# PSPS_AVNC_SRD_power-2020-09-19.net
KiCad netlist of a schematic drawn in EAGLE
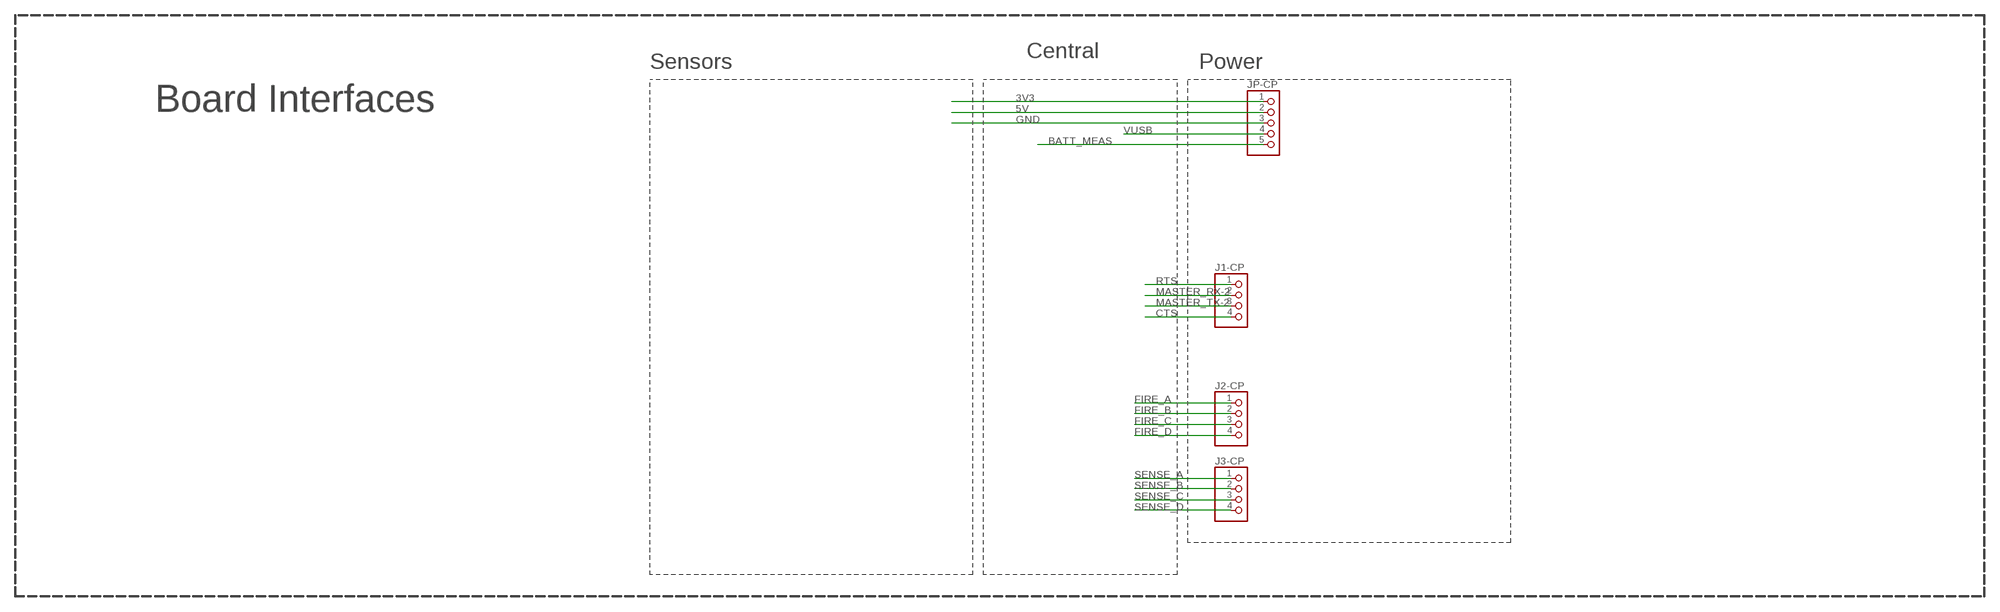
[diagram p0: schematic, sheet 1, part 1 of 3]
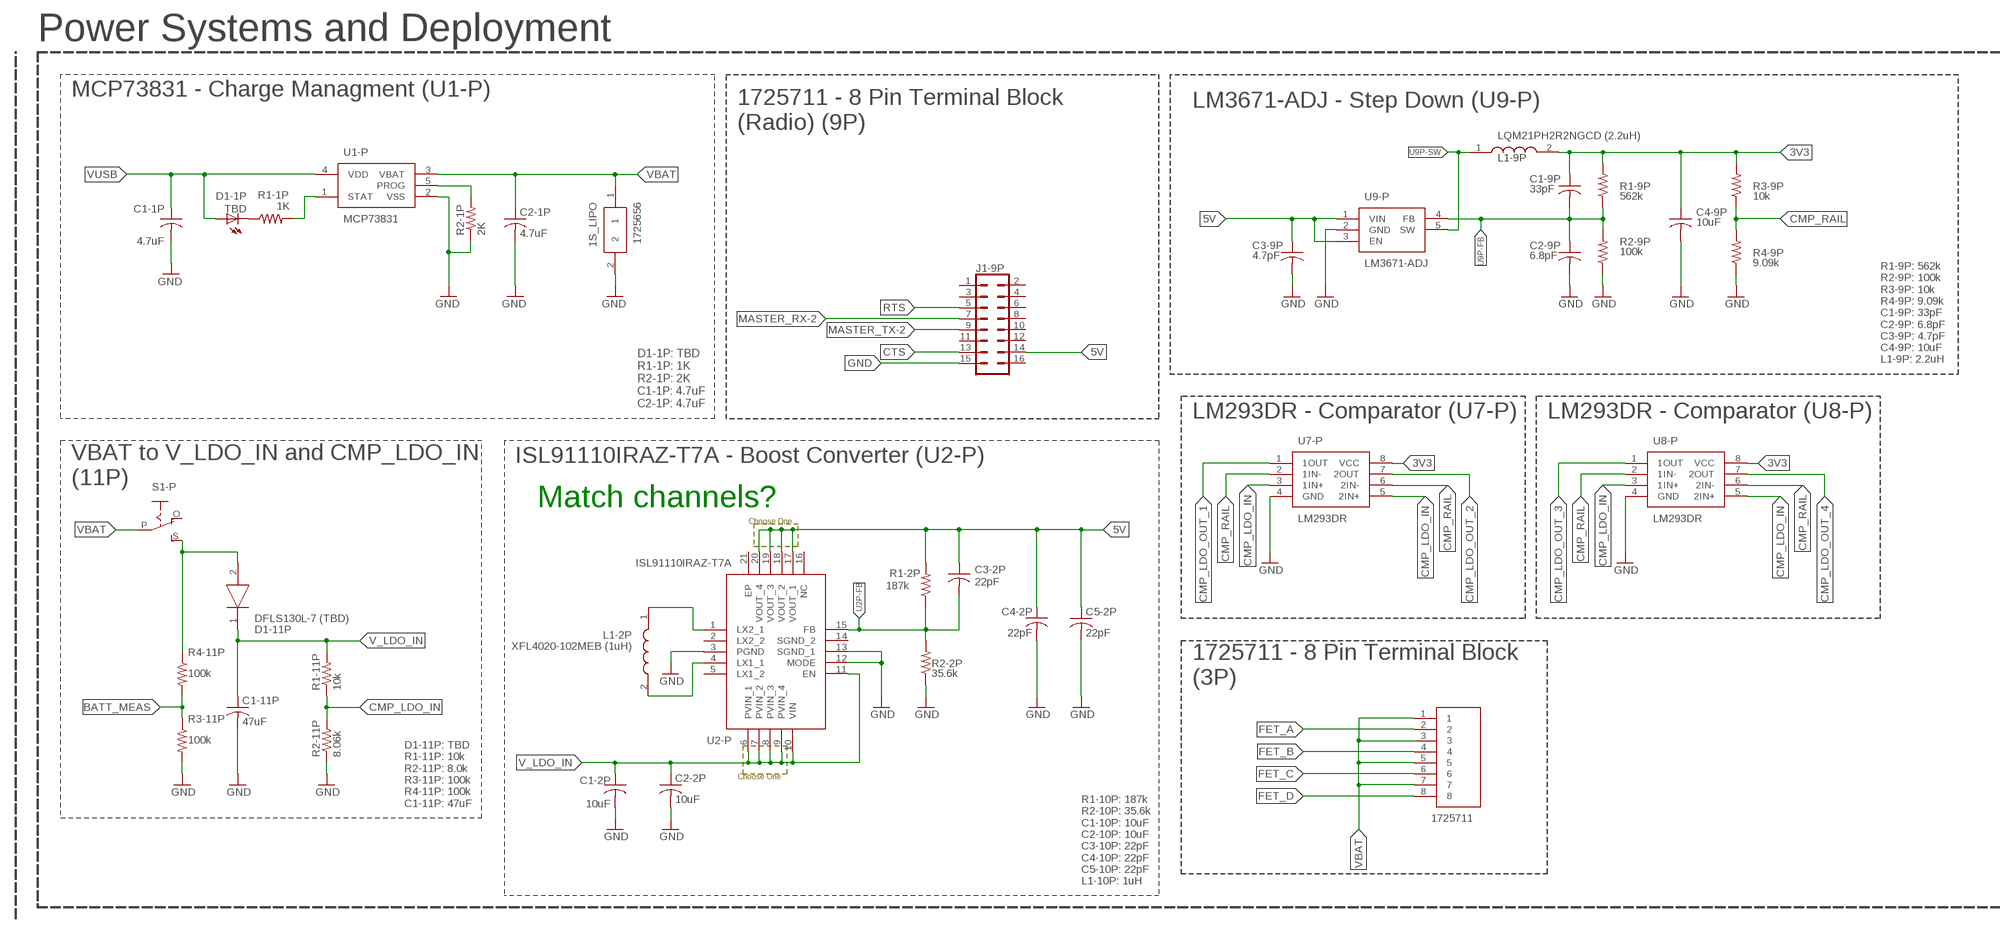
[diagram p1: schematic, sheet 1, part 2 of 3]
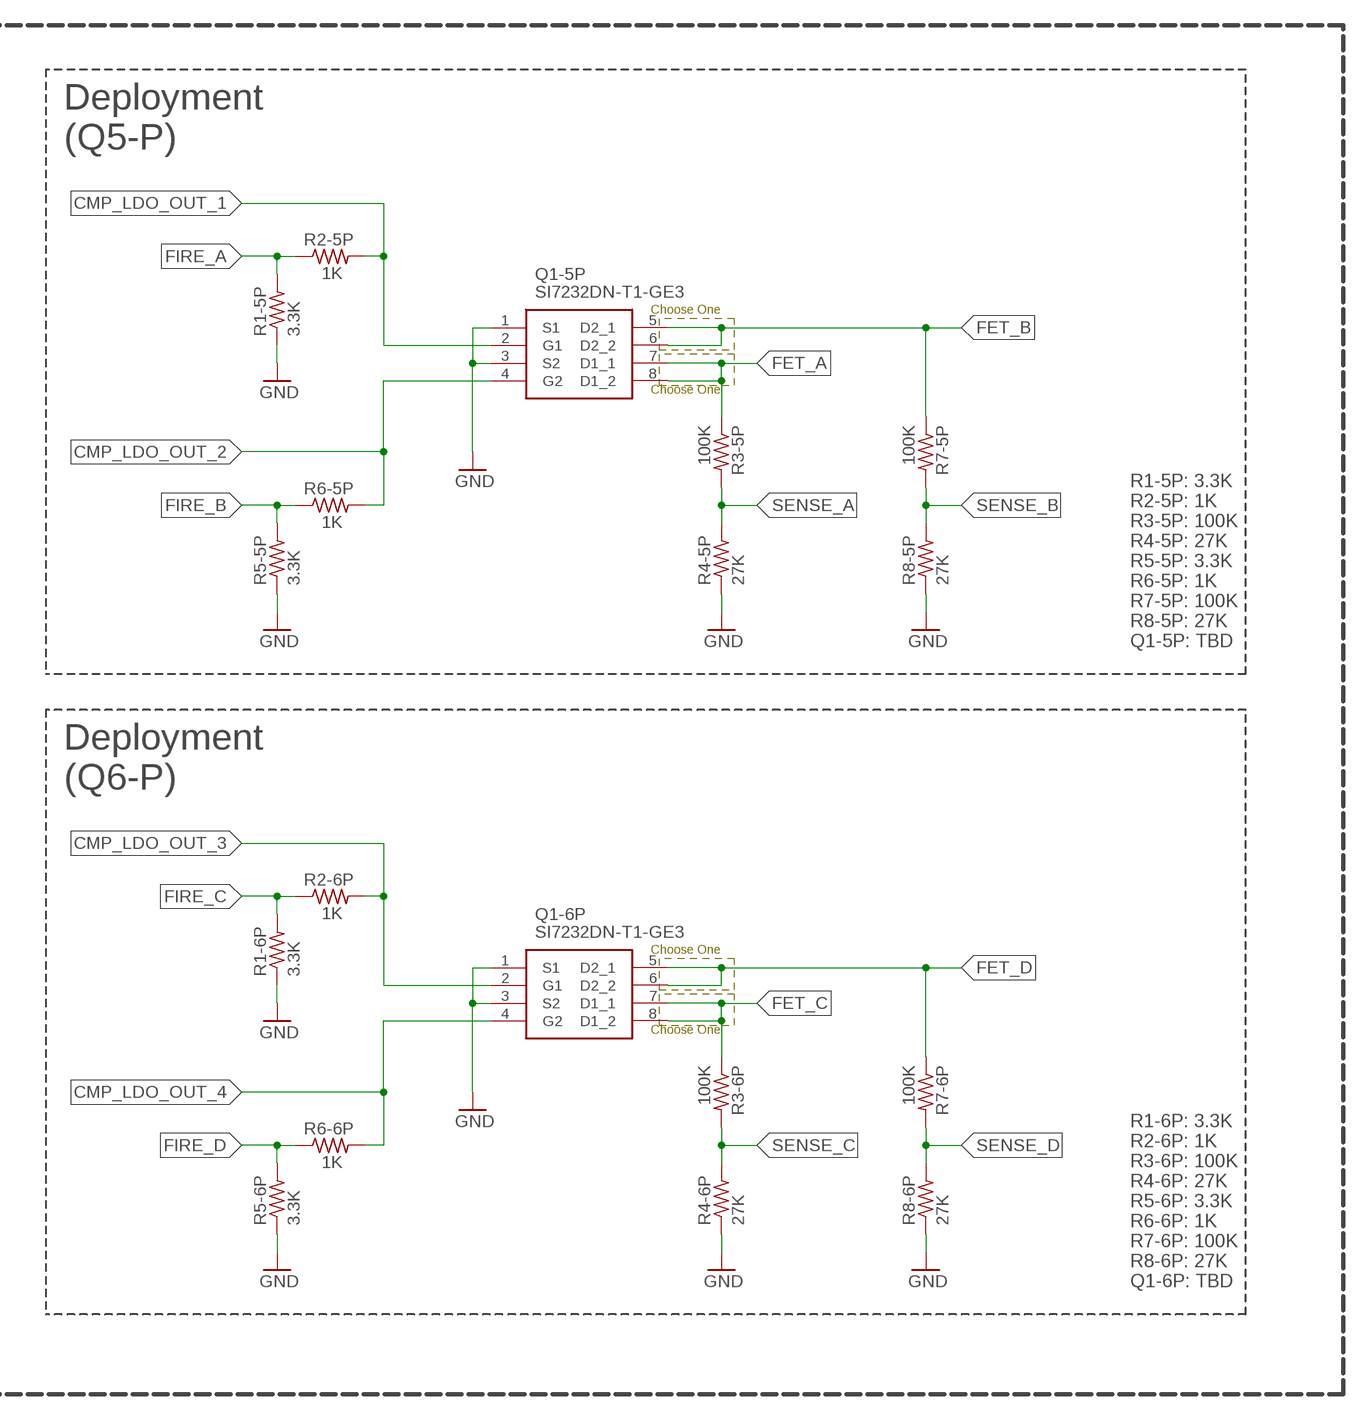
[diagram p2: schematic, sheet 1, part 3 of 3]

(export (version "E")
  (design (tool "Eeschema 10.0.6"))
  (components
    (comp (ref "1S_LIPO")
      (value "1725656")
      (footprint "eagle-import:1725656")
      (fields (field (name "MOUSER_PART_NUMBER") "651-1725656"))
      (libsource (lib "eagle-import") (part "1725656"))
    )
    (comp (ref "C1-1P")
      (value "4.7uF")
      (footprint "eagle-import:C0805")
      (libsource (lib "eagle-import") (part "resistor_348_C-USC0805"))
    )
    (comp (ref "C1-2P")
      (value "10uF")
      (footprint "eagle-import:C0805")
      (libsource (lib "eagle-import") (part "resistor_348_C-USC0805"))
    )
    (comp (ref "C1-9P")
      (value "33pF")
      (footprint "eagle-import:C0805")
      (libsource (lib "eagle-import") (part "resistor_348_C-USC0805"))
    )
    (comp (ref "C1-11P")
      (value "47uF")
      (footprint "eagle-import:C0805")
      (libsource (lib "eagle-import") (part "resistor_348_C-USC0805"))
    )
    (comp (ref "C2-1P")
      (value "4.7uF")
      (footprint "eagle-import:C0805")
      (libsource (lib "eagle-import") (part "resistor_348_C-USC0805"))
    )
    (comp (ref "C2-2P")
      (value "10uF")
      (footprint "eagle-import:C0805")
      (libsource (lib "eagle-import") (part "C-USC0805"))
    )
    (comp (ref "C2-9P")
      (value "6.8pF")
      (footprint "eagle-import:C0805")
      (libsource (lib "eagle-import") (part "resistor_348_C-USC0805"))
    )
    (comp (ref "C3-2P")
      (value "22pF")
      (footprint "eagle-import:C0805")
      (libsource (lib "eagle-import") (part "resistor_348_C-USC0805"))
    )
    (comp (ref "C3-9P")
      (value "4.7pF")
      (footprint "eagle-import:C0805")
      (libsource (lib "eagle-import") (part "resistor_348_C-USC0805"))
    )
    (comp (ref "C4-2P")
      (value "22pF")
      (footprint "eagle-import:C0805")
      (fields (field (name "SPICEPREFIX") "C"))
      (libsource (lib "eagle-import") (part "resistor_348_C-USC0805"))
    )
    (comp (ref "C4-9P")
      (value "10uF")
      (footprint "eagle-import:C0805")
      (libsource (lib "eagle-import") (part "resistor_348_C-USC0805"))
    )
    (comp (ref "C5-2P")
      (value "22pF")
      (footprint "eagle-import:C0805")
      (libsource (lib "eagle-import") (part "C-USC0805"))
    )
    (comp (ref "D1-1P")
      (value "TBD")
      (footprint "eagle-import:CHIPLED_0805")
      (libsource (lib "eagle-import") (part "LEDCHIPLED_0805"))
    )
    (comp (ref "D1-11P")
      (value "DFLS130L-7 (TBD)")
      (footprint "eagle-import:POWERDI_123")
      (fields
        (field (name "MANUFACTURER_PART_NUMBER") "DFLS130L-7")
        (field (name "MOUSER_PART_NUMBER") "621-DFLS130L")
      )
      (libsource (lib "eagle-import") (part "DFLS130L-7"))
    )
    (comp (ref "J1-9P")
      (value "CONN_08X2")
      (footprint "eagle-import:2X8")
      (libsource (lib "eagle-import") (part "CONN_08X2"))
    )
    (comp (ref "J1-CP")
      (value "PINHD-1X4")
      (footprint "eagle-import:1X04")
      (libsource (lib "eagle-import") (part "PINHD-1X4"))
    )
    (comp (ref "J2-CP")
      (value "PINHD-1X4")
      (footprint "eagle-import:1X04")
      (libsource (lib "eagle-import") (part "PINHD-1X4"))
    )
    (comp (ref "J2-P")
      (value "1725711")
      (footprint "eagle-import:1725711")
      (fields (field (name "MOUSER_PART_NUMBER") "651-1725711"))
      (libsource (lib "eagle-import") (part "1725711"))
    )
    (comp (ref "J3-CP")
      (value "PINHD-1X4")
      (footprint "eagle-import:1X04")
      (libsource (lib "eagle-import") (part "PINHD-1X4"))
    )
    (comp (ref "JP-CP")
      (value "PINHD-1X5")
      (footprint "eagle-import:1X05")
      (libsource (lib "eagle-import") (part "PINHD-1X5"))
    )
    (comp (ref "L1-2P")
      (value "XFL4020-102MEB (1uH)")
      (footprint "eagle-import:XFL4020")
      (fields
        (field (name "MANUFACTURER_PART_NUMBER") "XFL4020-102MEB")
        (field (name "MOUSER_PART_NUMBER") "994-XFL4020-102MEB")
      )
      (libsource (lib "eagle-import") (part "XFL4020-102MEB"))
    )
    (comp (ref "L1-9P")
      (value "LQM21PH2R2NGCD (2.2uH)")
      (footprint "eagle-import:INDC2012X100N")
      (fields
        (field (name "MANUFACTURER_PART_NUMBER") "LQM21PH2R2NGCD")
        (field (name "MOUSER_PART_NUMBER") "81-LQM21PH2R2NGCD")
      )
      (libsource (lib "eagle-import") (part "LQM21PH2R2NGCD"))
    )
    (comp (ref "Q1-5P")
      (value "SI7232DN-T1-GE3")
      (footprint "eagle-import:POWERPAK-1212-8")
      (fields (field (name "MOUSER_PART_NUMBER") "781-SI7232DN-GE3"))
      (libsource (lib "eagle-import") (part "SI7232DN-T1-GE3"))
    )
    (comp (ref "Q1-6P")
      (value "SI7232DN-T1-GE3")
      (footprint "eagle-import:POWERPAK-1212-8")
      (fields (field (name "MOUSER_PART_NUMBER") "781-SI7232DN-GE3"))
      (libsource (lib "eagle-import") (part "SI7232DN-T1-GE3"))
    )
    (comp (ref "R1-1P")
      (value "1K")
      (footprint "eagle-import:R0805")
      (libsource (lib "eagle-import") (part "resistor_348_R-US_R0805"))
    )
    (comp (ref "R1-2P")
      (value "187k")
      (footprint "eagle-import:R0805")
      (libsource (lib "eagle-import") (part "resistor_348_R-US_R0805"))
    )
    (comp (ref "R1-5P")
      (value "3.3K")
      (footprint "eagle-import:M0805")
      (libsource (lib "eagle-import") (part "rcl_334_R-US_M0805"))
    )
    (comp (ref "R1-6P")
      (value "3.3K")
      (footprint "eagle-import:M0805")
      (libsource (lib "eagle-import") (part "rcl_334_R-US_M0805"))
    )
    (comp (ref "R1-9P")
      (value "562k")
      (footprint "eagle-import:R0805")
      (libsource (lib "eagle-import") (part "resistor_348_R-US_R0805"))
    )
    (comp (ref "R1-11P")
      (value "10k")
      (footprint "eagle-import:R0805")
      (libsource (lib "eagle-import") (part "resistor_348_R-US_R0805"))
    )
    (comp (ref "R2-1P")
      (value "2K")
      (footprint "eagle-import:R0805")
      (libsource (lib "eagle-import") (part "resistor_348_R-US_R0805"))
    )
    (comp (ref "R2-2P")
      (value "35.6k")
      (footprint "eagle-import:R0805")
      (libsource (lib "eagle-import") (part "resistor_348_R-US_R0805"))
    )
    (comp (ref "R2-5P")
      (value "1K")
      (footprint "eagle-import:M0805")
      (libsource (lib "eagle-import") (part "rcl_334_R-US_M0805"))
    )
    (comp (ref "R2-6P")
      (value "1K")
      (footprint "eagle-import:M0805")
      (libsource (lib "eagle-import") (part "rcl_334_R-US_M0805"))
    )
    (comp (ref "R2-9P")
      (value "100k")
      (footprint "eagle-import:R0805")
      (libsource (lib "eagle-import") (part "resistor_348_R-US_R0805"))
    )
    (comp (ref "R2-11P")
      (value "8.06k")
      (footprint "eagle-import:R0805")
      (libsource (lib "eagle-import") (part "resistor_348_R-US_R0805"))
    )
    (comp (ref "R3-5P")
      (value "100K")
      (footprint "eagle-import:M0805")
      (libsource (lib "eagle-import") (part "rcl_334_R-US_M0805"))
    )
    (comp (ref "R3-6P")
      (value "100K")
      (footprint "eagle-import:M0805")
      (libsource (lib "eagle-import") (part "rcl_334_R-US_M0805"))
    )
    (comp (ref "R3-9P")
      (value "10k")
      (footprint "eagle-import:R0805")
      (libsource (lib "eagle-import") (part "resistor_348_R-US_R0805"))
    )
    (comp (ref "R3-11P")
      (value "100k")
      (footprint "eagle-import:R0805")
      (libsource (lib "eagle-import") (part "R-US_R0805"))
    )
    (comp (ref "R4-5P")
      (value "27K")
      (footprint "eagle-import:M0805")
      (libsource (lib "eagle-import") (part "rcl_334_R-US_M0805"))
    )
    (comp (ref "R4-6P")
      (value "27K")
      (footprint "eagle-import:M0805")
      (libsource (lib "eagle-import") (part "rcl_334_R-US_M0805"))
    )
    (comp (ref "R4-9P")
      (value "9.09k")
      (footprint "eagle-import:R0805")
      (libsource (lib "eagle-import") (part "resistor_348_R-US_R0805"))
    )
    (comp (ref "R4-11P")
      (value "100k")
      (footprint "eagle-import:R0805")
      (libsource (lib "eagle-import") (part "R-US_R0805"))
    )
    (comp (ref "R5-5P")
      (value "3.3K")
      (footprint "eagle-import:M0805")
      (libsource (lib "eagle-import") (part "rcl_334_R-US_M0805"))
    )
    (comp (ref "R5-6P")
      (value "3.3K")
      (footprint "eagle-import:M0805")
      (libsource (lib "eagle-import") (part "rcl_334_R-US_M0805"))
    )
    (comp (ref "R6-5P")
      (value "1K")
      (footprint "eagle-import:M0805")
      (libsource (lib "eagle-import") (part "rcl_334_R-US_M0805"))
    )
    (comp (ref "R6-6P")
      (value "1K")
      (footprint "eagle-import:M0805")
      (libsource (lib "eagle-import") (part "rcl_334_R-US_M0805"))
    )
    (comp (ref "R7-5P")
      (value "100K")
      (footprint "eagle-import:M0805")
      (libsource (lib "eagle-import") (part "rcl_334_R-US_M0805"))
    )
    (comp (ref "R7-6P")
      (value "100K")
      (footprint "eagle-import:M0805")
      (libsource (lib "eagle-import") (part "rcl_334_R-US_M0805"))
    )
    (comp (ref "R8-5P")
      (value "27K")
      (footprint "eagle-import:M0805")
      (libsource (lib "eagle-import") (part "rcl_334_R-US_M0805"))
    )
    (comp (ref "R8-6P")
      (value "27K")
      (footprint "eagle-import:M0805")
      (libsource (lib "eagle-import") (part "rcl_334_R-US_M0805"))
    )
    (comp (ref "S1-P")
      (value "EG1218S")
      (footprint "eagle-import:EG1218")
      (libsource (lib "eagle-import") (part "EG1218S"))
    )
    (comp (ref "U1-P")
      (value "MCP73831")
      (footprint "eagle-import:SOT95P270X145-5N")
      (fields
        (field (name "MANUFACTURER_PART_NUMBER") "MCP73831T-2ACI/OT")
        (field (name "MOUSER_PART_NUMBER") "579-MCP73831T-2ACIOT")
      )
      (libsource (lib "eagle-import") (part "MCP73831T-2ACI_OT"))
    )
    (comp (ref "U2-P")
      (value "ISL91110IRAZ-T7A")
      (footprint "eagle-import:QFN50P400X400X100-21N")
      (libsource (lib "eagle-import") (part "ISL91110IRAZ-T7A"))
    )
    (comp (ref "U7-P")
      (value "LM293DR")
      (footprint "eagle-import:SOIC127P600X175-8N")
      (fields (field (name "MOUSER_PART_NUMBER") "595-LM293DR"))
      (libsource (lib "eagle-import") (part "LM293DR"))
    )
    (comp (ref "U8-P")
      (value "LM293DR")
      (footprint "eagle-import:SOIC127P600X175-8N")
      (fields (field (name "MOUSER_PART_NUMBER") "595-LM293DR"))
      (libsource (lib "eagle-import") (part "LM293DR"))
    )
    (comp (ref "U9-P")
      (value "LM3671-ADJ")
      (footprint "eagle-import:SOT95P280X145-5N")
      (fields
        (field (name "MANUFACTURER_PART_NUMBER") "LM3671MFX-ADJ/NOPB")
        (field (name "MOUSER_PART_NUMBER") "926-LM3671MFXADJNOPB")
      )
      (libsource (lib "eagle-import") (part "LM3671MFX-ADJ_NOPB"))
    )
  )
  (nets
    (net (code "1") (name "3V3") (class "Default")
      (node (ref "C1-9P") (pin "1") (pinfunction "1_1") (pintype "passive"))
      (node (ref "C4-9P") (pin "1") (pinfunction "1_1") (pintype "passive"))
      (node (ref "JP-CP") (pin "1") (pinfunction "1_1") (pintype "passive"))
      (node (ref "L1-9P") (pin "2") (pinfunction "2_2") (pintype "bidirectional"))
      (node (ref "R1-9P") (pin "2") (pinfunction "2_2") (pintype "passive"))
      (node (ref "R3-9P") (pin "2") (pinfunction "2_2") (pintype "passive"))
      (node (ref "U7-P") (pin "8") (pinfunction "VCC_8") (pintype "bidirectional"))
      (node (ref "U8-P") (pin "8") (pinfunction "VCC_8") (pintype "bidirectional"))
    )
    (net (code "2") (name "5V") (class "Default")
      (node (ref "C3-2P") (pin "1") (pinfunction "1_1") (pintype "passive"))
      (node (ref "C3-9P") (pin "1") (pinfunction "1_1") (pintype "passive"))
      (node (ref "C4-2P") (pin "1") (pinfunction "1_1") (pintype "passive"))
      (node (ref "C5-2P") (pin "1") (pinfunction "1_1") (pintype "passive"))
      (node (ref "J1-9P") (pin "14") (pinfunction "14_14") (pintype "passive"))
      (node (ref "JP-CP") (pin "2") (pinfunction "2_2") (pintype "passive"))
      (node (ref "R1-2P") (pin "2") (pinfunction "2_2") (pintype "passive"))
      (node (ref "U2-P") (pin "17") (pinfunction "VOUT_1_17") (pintype "bidirectional"))
      (node (ref "U2-P") (pin "18") (pinfunction "VOUT_2_18") (pintype "bidirectional"))
      (node (ref "U2-P") (pin "19") (pinfunction "VOUT_3_19") (pintype "bidirectional"))
      (node (ref "U2-P") (pin "20") (pinfunction "VOUT_4_20") (pintype "bidirectional"))
      (node (ref "U9-P") (pin "1") (pinfunction "VIN_1") (pintype "bidirectional"))
      (node (ref "U9-P") (pin "3") (pinfunction "EN_3") (pintype "bidirectional"))
    )
    (net (code "3") (name "BATT_MEAS") (class "Default")
      (node (ref "JP-CP") (pin "5") (pinfunction "5_5") (pintype "passive"))
      (node (ref "R3-11P") (pin "1") (pinfunction "1_1") (pintype "passive"))
      (node (ref "R4-11P") (pin "2") (pinfunction "2_2") (pintype "passive"))
    )
    (net (code "4") (name "CMP_LDO_IN") (class "Default")
      (node (ref "R1-11P") (pin "1") (pinfunction "1_1") (pintype "passive"))
      (node (ref "R2-11P") (pin "2") (pinfunction "2_2") (pintype "passive"))
      (node (ref "U7-P") (pin "3") (pinfunction "1IN+_3") (pintype "bidirectional"))
      (node (ref "U7-P") (pin "5") (pinfunction "2IN+_5") (pintype "bidirectional"))
      (node (ref "U8-P") (pin "3") (pinfunction "1IN+_3") (pintype "bidirectional"))
      (node (ref "U8-P") (pin "5") (pinfunction "2IN+_5") (pintype "bidirectional"))
    )
    (net (code "5") (name "CMP_LDO_OUT_1") (class "Default")
      (node (ref "Q1-5P") (pin "2") (pinfunction "G1_2") (pintype "bidirectional"))
      (node (ref "R2-5P") (pin "2") (pinfunction "2_2") (pintype "passive"))
      (node (ref "U7-P") (pin "1") (pinfunction "1OUT_1") (pintype "bidirectional"))
    )
    (net (code "6") (name "CMP_LDO_OUT_2") (class "Default")
      (node (ref "Q1-5P") (pin "4") (pinfunction "G2_4") (pintype "bidirectional"))
      (node (ref "R6-5P") (pin "2") (pinfunction "2_2") (pintype "passive"))
      (node (ref "U7-P") (pin "7") (pinfunction "2OUT_7") (pintype "bidirectional"))
    )
    (net (code "7") (name "CMP_LDO_OUT_3") (class "Default")
      (node (ref "Q1-6P") (pin "2") (pinfunction "G1_2") (pintype "bidirectional"))
      (node (ref "R2-6P") (pin "2") (pinfunction "2_2") (pintype "passive"))
      (node (ref "U8-P") (pin "1") (pinfunction "1OUT_1") (pintype "bidirectional"))
    )
    (net (code "8") (name "CMP_LDO_OUT_4") (class "Default")
      (node (ref "Q1-6P") (pin "4") (pinfunction "G2_4") (pintype "bidirectional"))
      (node (ref "R6-6P") (pin "2") (pinfunction "2_2") (pintype "passive"))
      (node (ref "U8-P") (pin "7") (pinfunction "2OUT_7") (pintype "bidirectional"))
    )
    (net (code "9") (name "CMP_RAIL") (class "Default")
      (node (ref "R3-9P") (pin "1") (pinfunction "1_1") (pintype "passive"))
      (node (ref "R4-9P") (pin "2") (pinfunction "2_2") (pintype "passive"))
      (node (ref "U7-P") (pin "2") (pinfunction "1IN-_2") (pintype "bidirectional"))
      (node (ref "U7-P") (pin "6") (pinfunction "2IN-_6") (pintype "bidirectional"))
      (node (ref "U8-P") (pin "2") (pinfunction "1IN-_2") (pintype "bidirectional"))
      (node (ref "U8-P") (pin "6") (pinfunction "2IN-_6") (pintype "bidirectional"))
    )
    (net (code "10") (name "CTS") (class "Default")
      (node (ref "J1-9P") (pin "13") (pinfunction "13_13") (pintype "passive"))
      (node (ref "J1-CP") (pin "4") (pinfunction "4_4") (pintype "passive"))
    )
    (net (code "11") (name "FET_A") (class "Default")
      (node (ref "J2-P") (pin "2") (pinfunction "2_2") (pintype "bidirectional"))
      (node (ref "Q1-5P") (pin "7") (pinfunction "D1_1_7") (pintype "bidirectional"))
      (node (ref "Q1-5P") (pin "8") (pinfunction "D1_2_8") (pintype "bidirectional"))
      (node (ref "R3-5P") (pin "1") (pinfunction "1_1") (pintype "passive"))
    )
    (net (code "12") (name "FET_B") (class "Default")
      (node (ref "J2-P") (pin "4") (pinfunction "4_4") (pintype "bidirectional"))
      (node (ref "Q1-5P") (pin "5") (pinfunction "D2_1_5") (pintype "bidirectional"))
      (node (ref "Q1-5P") (pin "6") (pinfunction "D2_2_6") (pintype "bidirectional"))
      (node (ref "R7-5P") (pin "1") (pinfunction "1_1") (pintype "passive"))
    )
    (net (code "13") (name "FET_C") (class "Default")
      (node (ref "J2-P") (pin "6") (pinfunction "6_6") (pintype "bidirectional"))
      (node (ref "Q1-6P") (pin "7") (pinfunction "D1_1_7") (pintype "bidirectional"))
      (node (ref "Q1-6P") (pin "8") (pinfunction "D1_2_8") (pintype "bidirectional"))
      (node (ref "R3-6P") (pin "1") (pinfunction "1_1") (pintype "passive"))
    )
    (net (code "14") (name "FET_D") (class "Default")
      (node (ref "J2-P") (pin "8") (pinfunction "8_8") (pintype "bidirectional"))
      (node (ref "Q1-6P") (pin "5") (pinfunction "D2_1_5") (pintype "bidirectional"))
      (node (ref "Q1-6P") (pin "6") (pinfunction "D2_2_6") (pintype "bidirectional"))
      (node (ref "R7-6P") (pin "1") (pinfunction "1_1") (pintype "passive"))
    )
    (net (code "15") (name "FIRE_A") (class "Default")
      (node (ref "J2-CP") (pin "1") (pinfunction "1_1") (pintype "passive"))
      (node (ref "R1-5P") (pin "2") (pinfunction "2_2") (pintype "passive"))
      (node (ref "R2-5P") (pin "1") (pinfunction "1_1") (pintype "passive"))
    )
    (net (code "16") (name "FIRE_B") (class "Default")
      (node (ref "J2-CP") (pin "2") (pinfunction "2_2") (pintype "passive"))
      (node (ref "R5-5P") (pin "2") (pinfunction "2_2") (pintype "passive"))
      (node (ref "R6-5P") (pin "1") (pinfunction "1_1") (pintype "passive"))
    )
    (net (code "17") (name "FIRE_C") (class "Default")
      (node (ref "J2-CP") (pin "3") (pinfunction "3_3") (pintype "passive"))
      (node (ref "R1-6P") (pin "2") (pinfunction "2_2") (pintype "passive"))
      (node (ref "R2-6P") (pin "1") (pinfunction "1_1") (pintype "passive"))
    )
    (net (code "18") (name "FIRE_D") (class "Default")
      (node (ref "J2-CP") (pin "4") (pinfunction "4_4") (pintype "passive"))
      (node (ref "R5-6P") (pin "2") (pinfunction "2_2") (pintype "passive"))
      (node (ref "R6-6P") (pin "1") (pinfunction "1_1") (pintype "passive"))
    )
    (net (code "19") (name "GND") (class "Default")
      (node (ref "1S_LIPO") (pin "2") (pinfunction "2_2") (pintype "bidirectional"))
      (node (ref "C1-11P") (pin "2") (pinfunction "2_2") (pintype "passive"))
      (node (ref "C1-1P") (pin "2") (pinfunction "2_2") (pintype "passive"))
      (node (ref "C1-2P") (pin "2") (pinfunction "2_2") (pintype "passive"))
      (node (ref "C2-1P") (pin "2") (pinfunction "2_2") (pintype "passive"))
      (node (ref "C2-2P") (pin "2") (pinfunction "2_2") (pintype "passive"))
      (node (ref "C2-9P") (pin "2") (pinfunction "2_2") (pintype "passive"))
      (node (ref "C3-9P") (pin "2") (pinfunction "2_2") (pintype "passive"))
      (node (ref "C4-2P") (pin "2") (pinfunction "2_2") (pintype "passive"))
      (node (ref "C4-9P") (pin "2") (pinfunction "2_2") (pintype "passive"))
      (node (ref "C5-2P") (pin "2") (pinfunction "2_2") (pintype "passive"))
      (node (ref "J1-9P") (pin "15") (pinfunction "15_15") (pintype "passive"))
      (node (ref "JP-CP") (pin "3") (pinfunction "3_3") (pintype "passive"))
      (node (ref "Q1-5P") (pin "1") (pinfunction "S1_1") (pintype "bidirectional"))
      (node (ref "Q1-5P") (pin "3") (pinfunction "S2_3") (pintype "bidirectional"))
      (node (ref "Q1-6P") (pin "1") (pinfunction "S1_1") (pintype "bidirectional"))
      (node (ref "Q1-6P") (pin "3") (pinfunction "S2_3") (pintype "bidirectional"))
      (node (ref "R1-5P") (pin "1") (pinfunction "1_1") (pintype "passive"))
      (node (ref "R1-6P") (pin "1") (pinfunction "1_1") (pintype "passive"))
      (node (ref "R2-11P") (pin "1") (pinfunction "1_1") (pintype "passive"))
      (node (ref "R2-1P") (pin "1") (pinfunction "1_1") (pintype "passive"))
      (node (ref "R2-2P") (pin "1") (pinfunction "1_1") (pintype "passive"))
      (node (ref "R2-9P") (pin "1") (pinfunction "1_1") (pintype "passive"))
      (node (ref "R3-11P") (pin "2") (pinfunction "2_2") (pintype "passive"))
      (node (ref "R4-5P") (pin "1") (pinfunction "1_1") (pintype "passive"))
      (node (ref "R4-6P") (pin "1") (pinfunction "1_1") (pintype "passive"))
      (node (ref "R4-9P") (pin "1") (pinfunction "1_1") (pintype "passive"))
      (node (ref "R5-5P") (pin "1") (pinfunction "1_1") (pintype "passive"))
      (node (ref "R5-6P") (pin "1") (pinfunction "1_1") (pintype "passive"))
      (node (ref "R8-5P") (pin "1") (pinfunction "1_1") (pintype "passive"))
      (node (ref "R8-6P") (pin "1") (pinfunction "1_1") (pintype "passive"))
      (node (ref "U1-P") (pin "2") (pinfunction "VSS_2") (pintype "power_in"))
      (node (ref "U2-P") (pin "12") (pinfunction "MODE_12") (pintype "bidirectional"))
      (node (ref "U2-P") (pin "13") (pinfunction "SGND_1_13") (pintype "bidirectional"))
      (node (ref "U2-P") (pin "3") (pinfunction "PGND_3") (pintype "bidirectional"))
      (node (ref "U7-P") (pin "4") (pinfunction "GND_4") (pintype "bidirectional"))
      (node (ref "U8-P") (pin "4") (pinfunction "GND_4") (pintype "bidirectional"))
      (node (ref "U9-P") (pin "2") (pinfunction "GND_2") (pintype "bidirectional"))
    )
    (net (code "20") (name "MASTER_RX-2") (class "Default")
      (node (ref "J1-9P") (pin "7") (pinfunction "7_7") (pintype "passive"))
      (node (ref "J1-CP") (pin "2") (pinfunction "2_2") (pintype "passive"))
    )
    (net (code "21") (name "MASTER_TX-2") (class "Default")
      (node (ref "J1-9P") (pin "9") (pinfunction "9_9") (pintype "passive"))
      (node (ref "J1-CP") (pin "3") (pinfunction "3_3") (pintype "passive"))
    )
    (net (code "22") (name "Net-(D1-1P-PadC)") (class "Default")
      (node (ref "D1-1P") (pin "C") (pinfunction "C_C") (pintype "passive"))
      (node (ref "R1-1P") (pin "1") (pinfunction "1_1") (pintype "passive"))
    )
    (net (code "23") (name "Net-(D1-11P-A)") (class "Default")
      (node (ref "D1-11P") (pin "2") (pinfunction "A_2") (pintype "bidirectional"))
      (node (ref "R4-11P") (pin "1") (pinfunction "1_1") (pintype "passive"))
      (node (ref "S1-P") (pin "S") (pinfunction "S_S") (pintype "passive"))
    )
    (net (code "24") (name "Net-(U1-P-PROG)") (class "Default")
      (node (ref "R2-1P") (pin "2") (pinfunction "2_2") (pintype "passive"))
      (node (ref "U1-P") (pin "5") (pinfunction "PROG_5") (pintype "bidirectional"))
    )
    (net (code "25") (name "Net-(U1-P-STAT)") (class "Default")
      (node (ref "R1-1P") (pin "2") (pinfunction "2_2") (pintype "passive"))
      (node (ref "U1-P") (pin "1") (pinfunction "STAT_1") (pintype "bidirectional"))
    )
    (net (code "26") (name "Net-(U2-P-LX1_1)") (class "Default")
      (node (ref "L1-2P") (pin "2") (pinfunction "2_2") (pintype "bidirectional"))
      (node (ref "U2-P") (pin "4") (pinfunction "LX1_1_4") (pintype "bidirectional"))
    )
    (net (code "27") (name "Net-(U2-P-LX2_1)") (class "Default")
      (node (ref "L1-2P") (pin "1") (pinfunction "1_1") (pintype "bidirectional"))
      (node (ref "U2-P") (pin "1") (pinfunction "LX2_1_1") (pintype "bidirectional"))
    )
    (net (code "28") (name "RTS") (class "Default")
      (node (ref "J1-9P") (pin "5") (pinfunction "5_5") (pintype "passive"))
      (node (ref "J1-CP") (pin "1") (pinfunction "1_1") (pintype "passive"))
    )
    (net (code "29") (name "SENSE_A") (class "Default")
      (node (ref "J3-CP") (pin "1") (pinfunction "1_1") (pintype "passive"))
      (node (ref "R3-5P") (pin "2") (pinfunction "2_2") (pintype "passive"))
      (node (ref "R4-5P") (pin "2") (pinfunction "2_2") (pintype "passive"))
    )
    (net (code "30") (name "SENSE_B") (class "Default")
      (node (ref "J3-CP") (pin "2") (pinfunction "2_2") (pintype "passive"))
      (node (ref "R7-5P") (pin "2") (pinfunction "2_2") (pintype "passive"))
      (node (ref "R8-5P") (pin "2") (pinfunction "2_2") (pintype "passive"))
    )
    (net (code "31") (name "SENSE_C") (class "Default")
      (node (ref "J3-CP") (pin "3") (pinfunction "3_3") (pintype "passive"))
      (node (ref "R3-6P") (pin "2") (pinfunction "2_2") (pintype "passive"))
      (node (ref "R4-6P") (pin "2") (pinfunction "2_2") (pintype "passive"))
    )
    (net (code "32") (name "SENSE_D") (class "Default")
      (node (ref "J3-CP") (pin "4") (pinfunction "4_4") (pintype "passive"))
      (node (ref "R7-6P") (pin "2") (pinfunction "2_2") (pintype "passive"))
      (node (ref "R8-6P") (pin "2") (pinfunction "2_2") (pintype "passive"))
    )
    (net (code "33") (name "U2P-FB") (class "Default")
      (node (ref "C3-2P") (pin "2") (pinfunction "2_2") (pintype "passive"))
      (node (ref "R1-2P") (pin "1") (pinfunction "1_1") (pintype "passive"))
      (node (ref "R2-2P") (pin "2") (pinfunction "2_2") (pintype "passive"))
      (node (ref "U2-P") (pin "15") (pinfunction "FB_15") (pintype "bidirectional"))
    )
    (net (code "34") (name "U9P-FB") (class "Default")
      (node (ref "C1-9P") (pin "2") (pinfunction "2_2") (pintype "passive"))
      (node (ref "C2-9P") (pin "1") (pinfunction "1_1") (pintype "passive"))
      (node (ref "R1-9P") (pin "1") (pinfunction "1_1") (pintype "passive"))
      (node (ref "R2-9P") (pin "2") (pinfunction "2_2") (pintype "passive"))
      (node (ref "U9-P") (pin "4") (pinfunction "FB_4") (pintype "bidirectional"))
    )
    (net (code "35") (name "U9P-SW") (class "Default")
      (node (ref "L1-9P") (pin "1") (pinfunction "1_1") (pintype "bidirectional"))
      (node (ref "U9-P") (pin "5") (pinfunction "SW_5") (pintype "bidirectional"))
    )
    (net (code "36") (name "VBAT") (class "Default")
      (node (ref "1S_LIPO") (pin "1") (pinfunction "1_1") (pintype "bidirectional"))
      (node (ref "C2-1P") (pin "1") (pinfunction "1_1") (pintype "passive"))
      (node (ref "J2-P") (pin "1") (pinfunction "1_1") (pintype "bidirectional"))
      (node (ref "J2-P") (pin "3") (pinfunction "3_3") (pintype "bidirectional"))
      (node (ref "J2-P") (pin "5") (pinfunction "5_5") (pintype "bidirectional"))
      (node (ref "J2-P") (pin "7") (pinfunction "7_7") (pintype "bidirectional"))
      (node (ref "S1-P") (pin "P") (pinfunction "P_P") (pintype "passive"))
      (node (ref "U1-P") (pin "3") (pinfunction "VBAT_3") (pintype "bidirectional"))
    )
    (net (code "37") (name "VUSB") (class "Default")
      (node (ref "C1-1P") (pin "1") (pinfunction "1_1") (pintype "passive"))
      (node (ref "D1-1P") (pin "A") (pinfunction "A_A") (pintype "passive"))
      (node (ref "JP-CP") (pin "4") (pinfunction "4_4") (pintype "passive"))
      (node (ref "U1-P") (pin "4") (pinfunction "VDD_4") (pintype "power_in"))
    )
    (net (code "38") (name "V_LDO_IN") (class "Default")
      (node (ref "C1-11P") (pin "1") (pinfunction "1_1") (pintype "passive"))
      (node (ref "C1-2P") (pin "1") (pinfunction "1_1") (pintype "passive"))
      (node (ref "C2-2P") (pin "1") (pinfunction "1_1") (pintype "passive"))
      (node (ref "D1-11P") (pin "1") (pinfunction "K_1") (pintype "bidirectional"))
      (node (ref "R1-11P") (pin "2") (pinfunction "2_2") (pintype "passive"))
      (node (ref "U2-P") (pin "10") (pinfunction "VIN_10") (pintype "bidirectional"))
      (node (ref "U2-P") (pin "11") (pinfunction "EN_11") (pintype "bidirectional"))
      (node (ref "U2-P") (pin "6") (pinfunction "PVIN_1_6") (pintype "bidirectional"))
      (node (ref "U2-P") (pin "7") (pinfunction "PVIN_2_7") (pintype "bidirectional"))
      (node (ref "U2-P") (pin "8") (pinfunction "PVIN_3_8") (pintype "bidirectional"))
      (node (ref "U2-P") (pin "9") (pinfunction "PVIN_4_9") (pintype "bidirectional"))
    )
    (net (code "39") (name "unconnected-(J1-9P-Pad1)") (class "Default")
      (node (ref "J1-9P") (pin "1") (pinfunction "1_1") (pintype "passive"))
    )
    (net (code "40") (name "unconnected-(J1-9P-Pad2)") (class "Default")
      (node (ref "J1-9P") (pin "2") (pinfunction "2_2") (pintype "passive"))
    )
    (net (code "41") (name "unconnected-(J1-9P-Pad3)") (class "Default")
      (node (ref "J1-9P") (pin "3") (pinfunction "3_3") (pintype "passive"))
    )
    (net (code "42") (name "unconnected-(J1-9P-Pad4)") (class "Default")
      (node (ref "J1-9P") (pin "4") (pinfunction "4_4") (pintype "passive"))
    )
    (net (code "43") (name "unconnected-(J1-9P-Pad6)") (class "Default")
      (node (ref "J1-9P") (pin "6") (pinfunction "6_6") (pintype "passive"))
    )
    (net (code "44") (name "unconnected-(J1-9P-Pad8)") (class "Default")
      (node (ref "J1-9P") (pin "8") (pinfunction "8_8") (pintype "passive"))
    )
    (net (code "45") (name "unconnected-(J1-9P-Pad10)") (class "Default")
      (node (ref "J1-9P") (pin "10") (pinfunction "10_10") (pintype "passive"))
    )
    (net (code "46") (name "unconnected-(J1-9P-Pad11)") (class "Default")
      (node (ref "J1-9P") (pin "11") (pinfunction "11_11") (pintype "passive"))
    )
    (net (code "47") (name "unconnected-(J1-9P-Pad12)") (class "Default")
      (node (ref "J1-9P") (pin "12") (pinfunction "12_12") (pintype "passive"))
    )
    (net (code "48") (name "unconnected-(J1-9P-Pad16)") (class "Default")
      (node (ref "J1-9P") (pin "16") (pinfunction "16_16") (pintype "passive"))
    )
    (net (code "49") (name "unconnected-(S1-P-PadO)") (class "Default")
      (node (ref "S1-P") (pin "O") (pinfunction "O_O") (pintype "passive"))
    )
    (net (code "50") (name "unconnected-(U2-P-EP-Pad21)") (class "Default")
      (node (ref "U2-P") (pin "21") (pinfunction "EP_21") (pintype "bidirectional"))
    )
    (net (code "51") (name "unconnected-(U2-P-LX1_2-Pad5)") (class "Default")
      (node (ref "U2-P") (pin "5") (pinfunction "LX1_2_5") (pintype "bidirectional"))
    )
    (net (code "52") (name "unconnected-(U2-P-LX2_2-Pad2)") (class "Default")
      (node (ref "U2-P") (pin "2") (pinfunction "LX2_2_2") (pintype "bidirectional"))
    )
    (net (code "53") (name "unconnected-(U2-P-NC-Pad16)") (class "Default")
      (node (ref "U2-P") (pin "16") (pinfunction "NC_16") (pintype "no_connect"))
    )
    (net (code "54") (name "unconnected-(U2-P-SGND_2-Pad14)") (class "Default")
      (node (ref "U2-P") (pin "14") (pinfunction "SGND_2_14") (pintype "bidirectional"))
    )
  )
)
